# I2CHubLogicLevel.net
KiCad netlist of a schematic drawn in EAGLE
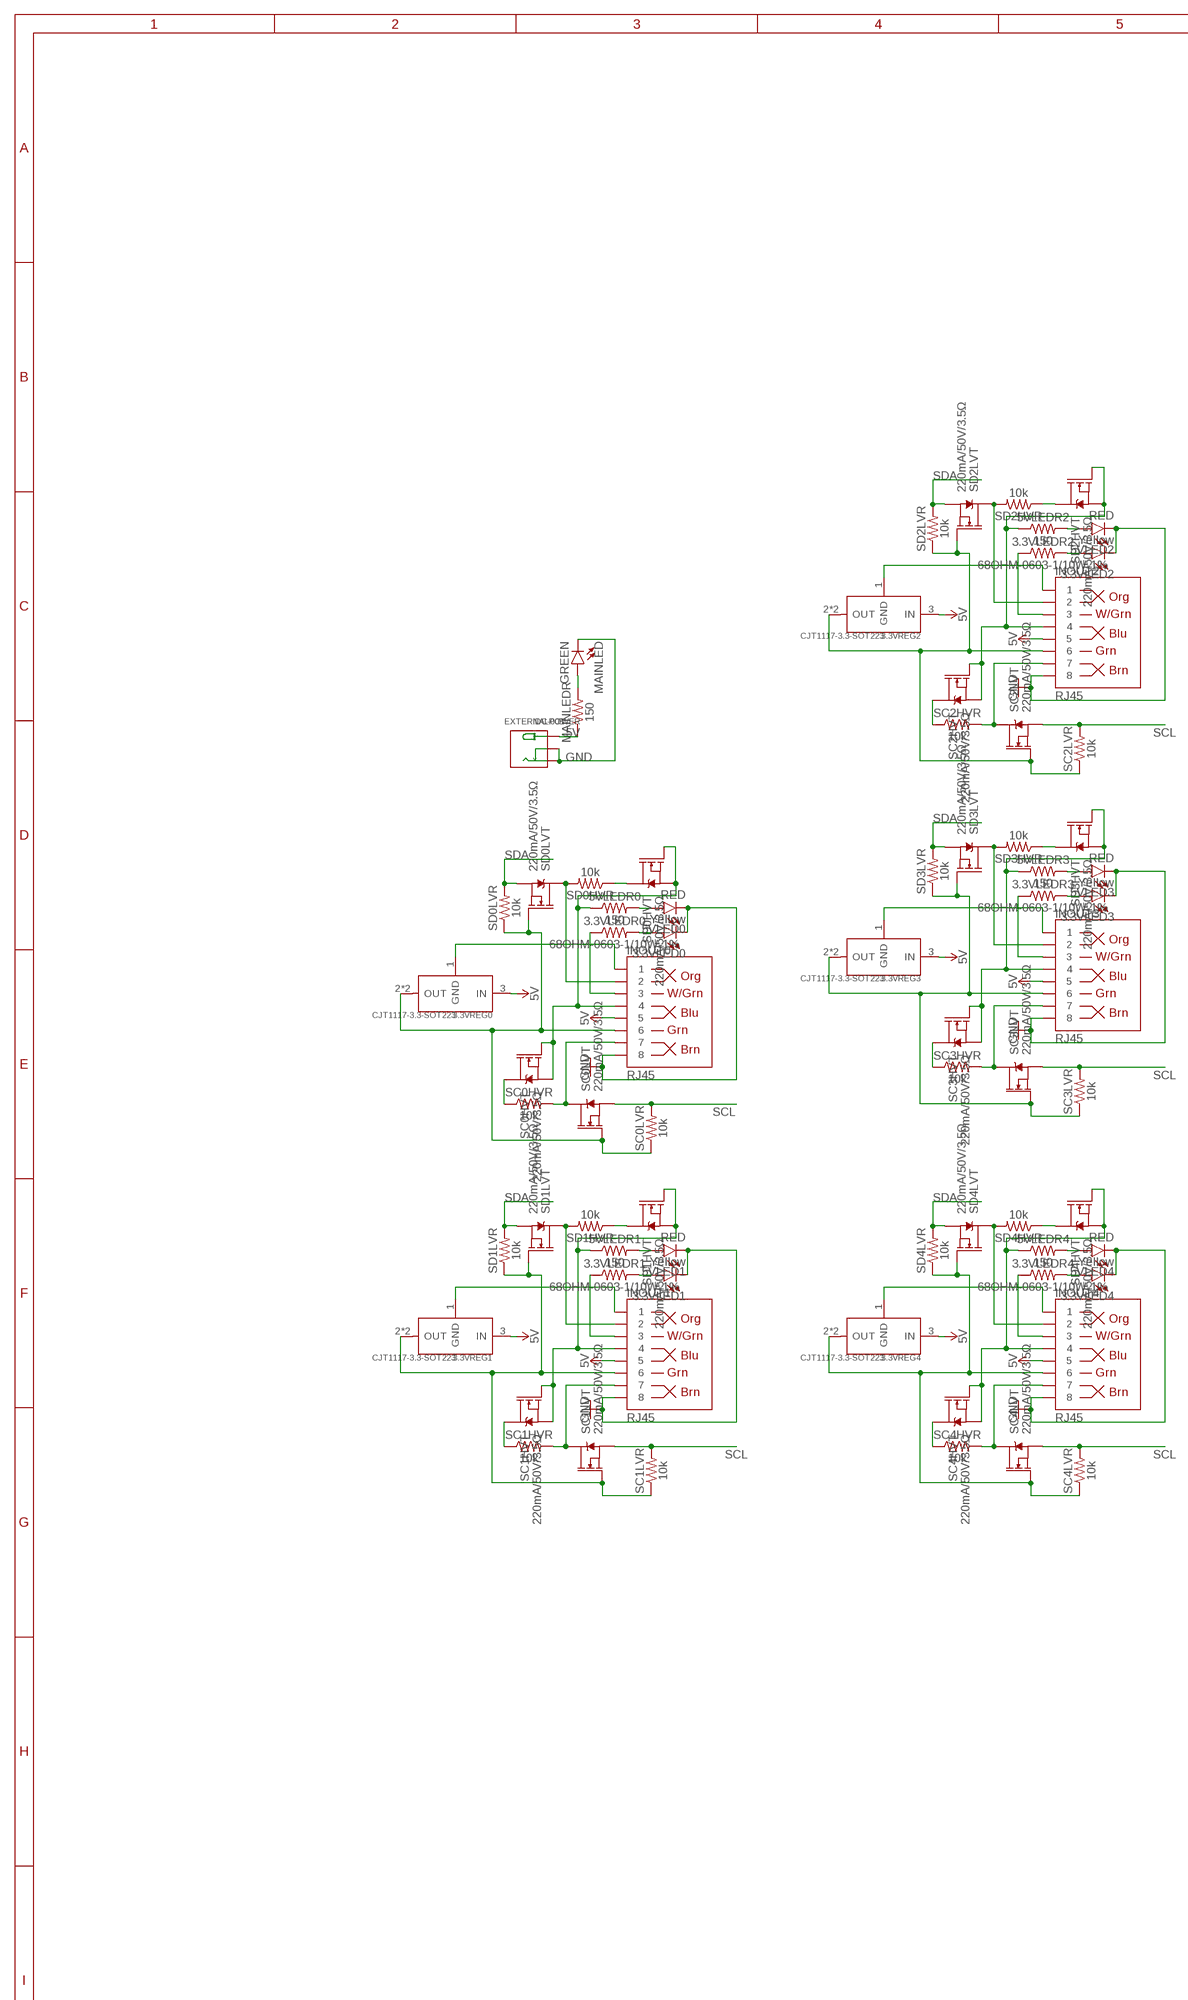
[diagram p0: schematic, sheet 1, part 1 of 2]
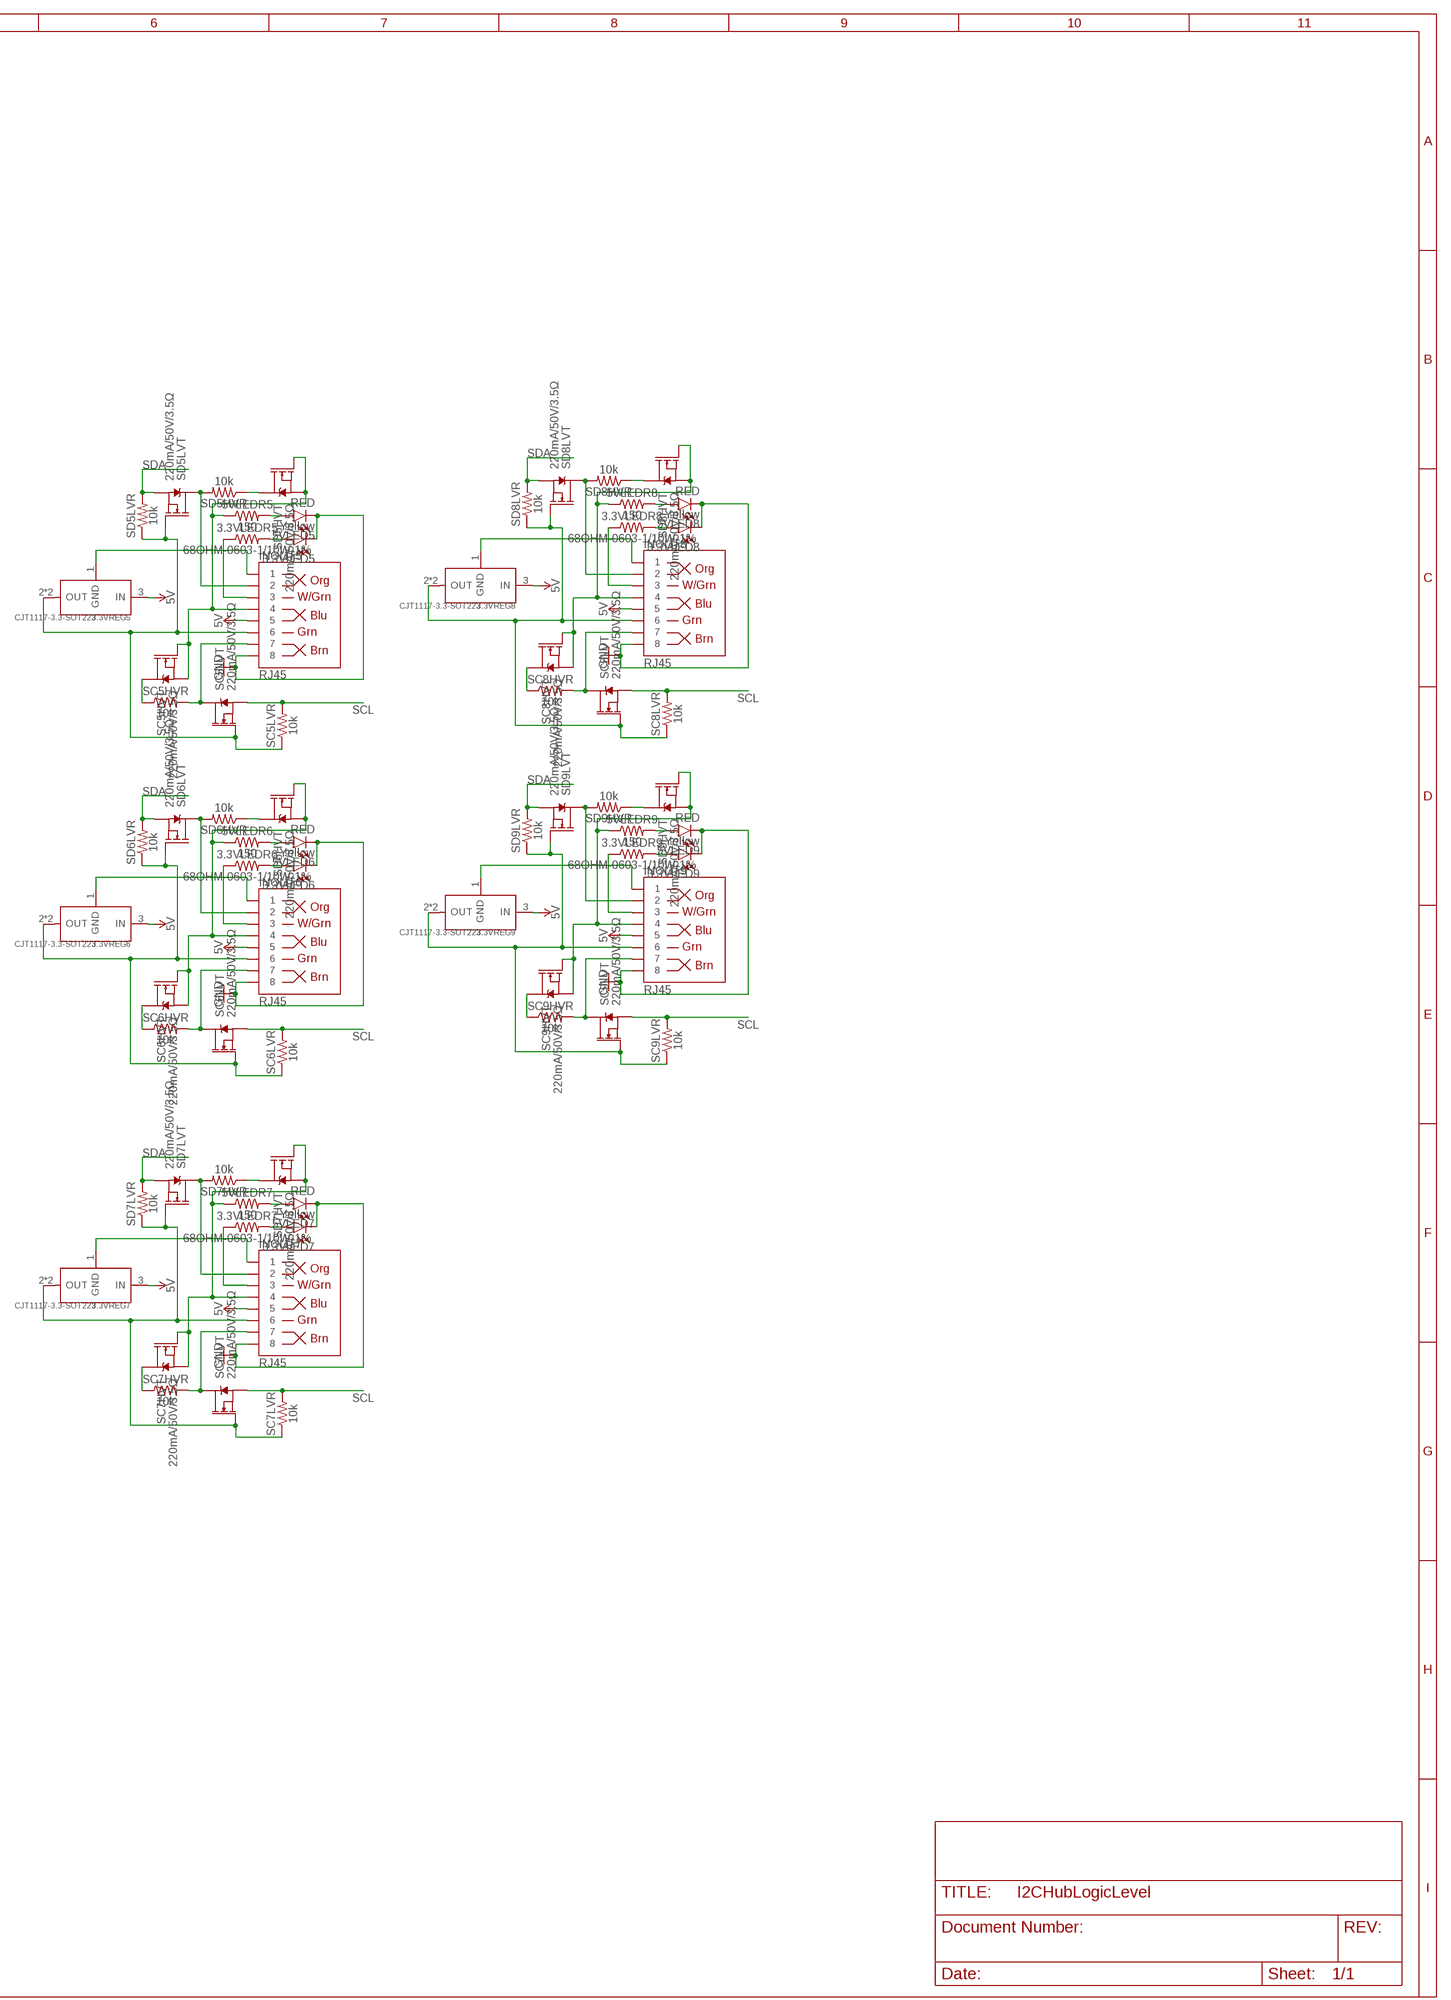
[diagram p1: schematic, sheet 1, part 2 of 2]

(export (version "E")
  (design (tool "Eeschema 10.0.6"))
  (components
    (comp (ref "3.3VLED0")
      (value "Yellow")
      (footprint "eagle-import:LED-0603")
      (libsource (lib "eagle-import") (part "LED-YELLOW0603"))
    )
    (comp (ref "3.3VLED1")
      (value "Yellow")
      (footprint "eagle-import:LED-0603")
      (libsource (lib "eagle-import") (part "LED-YELLOW0603"))
    )
    (comp (ref "3.3VLED2")
      (value "Yellow")
      (footprint "eagle-import:LED-0603")
      (libsource (lib "eagle-import") (part "LED-YELLOW0603"))
    )
    (comp (ref "3.3VLED3")
      (value "Yellow")
      (footprint "eagle-import:LED-0603")
      (libsource (lib "eagle-import") (part "LED-YELLOW0603"))
    )
    (comp (ref "3.3VLED4")
      (value "Yellow")
      (footprint "eagle-import:LED-0603")
      (libsource (lib "eagle-import") (part "LED-YELLOW0603"))
    )
    (comp (ref "3.3VLED5")
      (value "Yellow")
      (footprint "eagle-import:LED-0603")
      (libsource (lib "eagle-import") (part "LED-YELLOW0603"))
    )
    (comp (ref "3.3VLED6")
      (value "Yellow")
      (footprint "eagle-import:LED-0603")
      (libsource (lib "eagle-import") (part "LED-YELLOW0603"))
    )
    (comp (ref "3.3VLED7")
      (value "Yellow")
      (footprint "eagle-import:LED-0603")
      (libsource (lib "eagle-import") (part "LED-YELLOW0603"))
    )
    (comp (ref "3.3VLED8")
      (value "Yellow")
      (footprint "eagle-import:LED-0603")
      (libsource (lib "eagle-import") (part "LED-YELLOW0603"))
    )
    (comp (ref "3.3VLED9")
      (value "Yellow")
      (footprint "eagle-import:LED-0603")
      (libsource (lib "eagle-import") (part "LED-YELLOW0603"))
    )
    (comp (ref "3.3VLEDR0")
      (value "68OHM-0603-1/10W-1%")
      (footprint "eagle-import:0603")
      (libsource (lib "eagle-import") (part "68OHM-0603-1/10W-1%"))
    )
    (comp (ref "3.3VLEDR1")
      (value "68OHM-0603-1/10W-1%")
      (footprint "eagle-import:0603")
      (libsource (lib "eagle-import") (part "68OHM-0603-1/10W-1%"))
    )
    (comp (ref "3.3VLEDR2")
      (value "68OHM-0603-1/10W-1%")
      (footprint "eagle-import:0603")
      (libsource (lib "eagle-import") (part "68OHM-0603-1/10W-1%"))
    )
    (comp (ref "3.3VLEDR3")
      (value "68OHM-0603-1/10W-1%")
      (footprint "eagle-import:0603")
      (libsource (lib "eagle-import") (part "68OHM-0603-1/10W-1%"))
    )
    (comp (ref "3.3VLEDR4")
      (value "68OHM-0603-1/10W-1%")
      (footprint "eagle-import:0603")
      (libsource (lib "eagle-import") (part "68OHM-0603-1/10W-1%"))
    )
    (comp (ref "3.3VLEDR5")
      (value "68OHM-0603-1/10W-1%")
      (footprint "eagle-import:0603")
      (libsource (lib "eagle-import") (part "68OHM-0603-1/10W-1%"))
    )
    (comp (ref "3.3VLEDR6")
      (value "68OHM-0603-1/10W-1%")
      (footprint "eagle-import:0603")
      (libsource (lib "eagle-import") (part "68OHM-0603-1/10W-1%"))
    )
    (comp (ref "3.3VLEDR7")
      (value "68OHM-0603-1/10W-1%")
      (footprint "eagle-import:0603")
      (libsource (lib "eagle-import") (part "68OHM-0603-1/10W-1%"))
    )
    (comp (ref "3.3VLEDR8")
      (value "68OHM-0603-1/10W-1%")
      (footprint "eagle-import:0603")
      (libsource (lib "eagle-import") (part "68OHM-0603-1/10W-1%"))
    )
    (comp (ref "3.3VLEDR9")
      (value "68OHM-0603-1/10W-1%")
      (footprint "eagle-import:0603")
      (libsource (lib "eagle-import") (part "68OHM-0603-1/10W-1%"))
    )
    (comp (ref "3.3VREG0")
      (value "CJT1117-3.3-SOT223")
      (footprint "eagle-import:SOT-223")
      (fields (field (name "MPN") "CJT1117-3.3"))
      (libsource (lib "eagle-import") (part "PMIC-CJT1117-3.3(SOT223)"))
    )
    (comp (ref "3.3VREG1")
      (value "CJT1117-3.3-SOT223")
      (footprint "eagle-import:SOT-223")
      (fields (field (name "MPN") "CJT1117-3.3"))
      (libsource (lib "eagle-import") (part "PMIC-CJT1117-3.3(SOT223)"))
    )
    (comp (ref "3.3VREG2")
      (value "CJT1117-3.3-SOT223")
      (footprint "eagle-import:SOT-223")
      (fields (field (name "MPN") "CJT1117-3.3"))
      (libsource (lib "eagle-import") (part "PMIC-CJT1117-3.3(SOT223)"))
    )
    (comp (ref "3.3VREG3")
      (value "CJT1117-3.3-SOT223")
      (footprint "eagle-import:SOT-223")
      (fields (field (name "MPN") "CJT1117-3.3"))
      (libsource (lib "eagle-import") (part "PMIC-CJT1117-3.3(SOT223)"))
    )
    (comp (ref "3.3VREG4")
      (value "CJT1117-3.3-SOT223")
      (footprint "eagle-import:SOT-223")
      (fields (field (name "MPN") "CJT1117-3.3"))
      (libsource (lib "eagle-import") (part "PMIC-CJT1117-3.3(SOT223)"))
    )
    (comp (ref "3.3VREG5")
      (value "CJT1117-3.3-SOT223")
      (footprint "eagle-import:SOT-223")
      (fields (field (name "MPN") "CJT1117-3.3"))
      (libsource (lib "eagle-import") (part "PMIC-CJT1117-3.3(SOT223)"))
    )
    (comp (ref "3.3VREG6")
      (value "CJT1117-3.3-SOT223")
      (footprint "eagle-import:SOT-223")
      (fields (field (name "MPN") "CJT1117-3.3"))
      (libsource (lib "eagle-import") (part "PMIC-CJT1117-3.3(SOT223)"))
    )
    (comp (ref "3.3VREG7")
      (value "CJT1117-3.3-SOT223")
      (footprint "eagle-import:SOT-223")
      (fields (field (name "MPN") "CJT1117-3.3"))
      (libsource (lib "eagle-import") (part "PMIC-CJT1117-3.3(SOT223)"))
    )
    (comp (ref "3.3VREG8")
      (value "CJT1117-3.3-SOT223")
      (footprint "eagle-import:SOT-223")
      (fields (field (name "MPN") "CJT1117-3.3"))
      (libsource (lib "eagle-import") (part "PMIC-CJT1117-3.3(SOT223)"))
    )
    (comp (ref "3.3VREG9")
      (value "CJT1117-3.3-SOT223")
      (footprint "eagle-import:SOT-223")
      (fields (field (name "MPN") "CJT1117-3.3"))
      (libsource (lib "eagle-import") (part "PMIC-CJT1117-3.3(SOT223)"))
    )
    (comp (ref "5VLED0")
      (value "RED")
      (footprint "eagle-import:LED-0603")
      (libsource (lib "eagle-import") (part "LED-RED0603"))
    )
    (comp (ref "5VLED1")
      (value "RED")
      (footprint "eagle-import:LED-0603")
      (libsource (lib "eagle-import") (part "LED-RED0603"))
    )
    (comp (ref "5VLED2")
      (value "RED")
      (footprint "eagle-import:LED-0603")
      (libsource (lib "eagle-import") (part "LED-RED0603"))
    )
    (comp (ref "5VLED3")
      (value "RED")
      (footprint "eagle-import:LED-0603")
      (libsource (lib "eagle-import") (part "LED-RED0603"))
    )
    (comp (ref "5VLED4")
      (value "RED")
      (footprint "eagle-import:LED-0603")
      (libsource (lib "eagle-import") (part "LED-RED0603"))
    )
    (comp (ref "5VLED5")
      (value "RED")
      (footprint "eagle-import:LED-0603")
      (libsource (lib "eagle-import") (part "LED-RED0603"))
    )
    (comp (ref "5VLED6")
      (value "RED")
      (footprint "eagle-import:LED-0603")
      (libsource (lib "eagle-import") (part "LED-RED0603"))
    )
    (comp (ref "5VLED7")
      (value "RED")
      (footprint "eagle-import:LED-0603")
      (libsource (lib "eagle-import") (part "LED-RED0603"))
    )
    (comp (ref "5VLED8")
      (value "RED")
      (footprint "eagle-import:LED-0603")
      (libsource (lib "eagle-import") (part "LED-RED0603"))
    )
    (comp (ref "5VLED9")
      (value "RED")
      (footprint "eagle-import:LED-0603")
      (libsource (lib "eagle-import") (part "LED-RED0603"))
    )
    (comp (ref "5VLEDR0")
      (value "150")
      (footprint "eagle-import:0603")
      (libsource (lib "eagle-import") (part "150OHM-0603-1/10W-1%"))
    )
    (comp (ref "5VLEDR1")
      (value "150")
      (footprint "eagle-import:0603")
      (libsource (lib "eagle-import") (part "150OHM-0603-1/10W-1%"))
    )
    (comp (ref "5VLEDR2")
      (value "150")
      (footprint "eagle-import:0603")
      (libsource (lib "eagle-import") (part "150OHM-0603-1/10W-1%"))
    )
    (comp (ref "5VLEDR3")
      (value "150")
      (footprint "eagle-import:0603")
      (libsource (lib "eagle-import") (part "150OHM-0603-1/10W-1%"))
    )
    (comp (ref "5VLEDR4")
      (value "150")
      (footprint "eagle-import:0603")
      (libsource (lib "eagle-import") (part "150OHM-0603-1/10W-1%"))
    )
    (comp (ref "5VLEDR5")
      (value "150")
      (footprint "eagle-import:0603")
      (libsource (lib "eagle-import") (part "150OHM-0603-1/10W-1%"))
    )
    (comp (ref "5VLEDR6")
      (value "150")
      (footprint "eagle-import:0603")
      (libsource (lib "eagle-import") (part "150OHM-0603-1/10W-1%"))
    )
    (comp (ref "5VLEDR7")
      (value "150")
      (footprint "eagle-import:0603")
      (libsource (lib "eagle-import") (part "150OHM-0603-1/10W-1%"))
    )
    (comp (ref "5VLEDR8")
      (value "150")
      (footprint "eagle-import:0603")
      (libsource (lib "eagle-import") (part "150OHM-0603-1/10W-1%"))
    )
    (comp (ref "5VLEDR9")
      (value "150")
      (footprint "eagle-import:0603")
      (libsource (lib "eagle-import") (part "150OHM-0603-1/10W-1%"))
    )
    (comp (ref "EXTERNALPOWER")
      (value "DC-005")
      (footprint "eagle-import:DCJ3P-14.2X11.0X9.0MM")
      (libsource (lib "eagle-import") (part "CONN-POWER-JACK-2.1MM(DC-005)"))
    )
    (comp (ref "INOUT0")
      (value "RJ45")
      (footprint "eagle-import:RJ45-8")
      (libsource (lib "eagle-import") (part "RJ45-8"))
    )
    (comp (ref "INOUT1")
      (value "RJ45")
      (footprint "eagle-import:RJ45-8")
      (libsource (lib "eagle-import") (part "RJ45-8"))
    )
    (comp (ref "INOUT2")
      (value "RJ45")
      (footprint "eagle-import:RJ45-8")
      (libsource (lib "eagle-import") (part "RJ45-8"))
    )
    (comp (ref "INOUT3")
      (value "RJ45")
      (footprint "eagle-import:RJ45-8")
      (libsource (lib "eagle-import") (part "RJ45-8"))
    )
    (comp (ref "INOUT4")
      (value "RJ45")
      (footprint "eagle-import:RJ45-8")
      (libsource (lib "eagle-import") (part "RJ45-8"))
    )
    (comp (ref "INOUT5")
      (value "RJ45")
      (footprint "eagle-import:RJ45-8")
      (libsource (lib "eagle-import") (part "RJ45-8"))
    )
    (comp (ref "INOUT6")
      (value "RJ45")
      (footprint "eagle-import:RJ45-8")
      (libsource (lib "eagle-import") (part "RJ45-8"))
    )
    (comp (ref "INOUT7")
      (value "RJ45")
      (footprint "eagle-import:RJ45-8")
      (libsource (lib "eagle-import") (part "RJ45-8"))
    )
    (comp (ref "INOUT8")
      (value "RJ45")
      (footprint "eagle-import:RJ45-8")
      (libsource (lib "eagle-import") (part "RJ45-8"))
    )
    (comp (ref "INOUT9")
      (value "RJ45")
      (footprint "eagle-import:RJ45-8")
      (libsource (lib "eagle-import") (part "RJ45-8"))
    )
    (comp (ref "MAINLED")
      (value "GREEN")
      (footprint "eagle-import:LED-0603")
      (libsource (lib "eagle-import") (part "LED-GREEN0603"))
    )
    (comp (ref "MAINLEDR")
      (value "150")
      (footprint "eagle-import:0603")
      (libsource (lib "eagle-import") (part "150OHM-0603-1/10W-1%"))
    )
    (comp (ref "SC0HVR")
      (value "10k")
      (footprint "eagle-import:0603")
      (libsource (lib "eagle-import") (part "10KOHM-0603-1/10W-1%"))
    )
    (comp (ref "SC0HVT")
      (value "220mA/50V/3.5Ω")
      (footprint "eagle-import:SOT23-3")
      (libsource (lib "eagle-import") (part "MOSFET-NCH-BSS138"))
    )
    (comp (ref "SC0LVR")
      (value "10k")
      (footprint "eagle-import:0603")
      (libsource (lib "eagle-import") (part "10KOHM-0603-1/10W-1%"))
    )
    (comp (ref "SC0LVT")
      (value "220mA/50V/3.5Ω")
      (footprint "eagle-import:SOT23-3")
      (libsource (lib "eagle-import") (part "MOSFET-NCH-BSS138"))
    )
    (comp (ref "SC1HVR")
      (value "10k")
      (footprint "eagle-import:0603")
      (libsource (lib "eagle-import") (part "10KOHM-0603-1/10W-1%"))
    )
    (comp (ref "SC1HVT")
      (value "220mA/50V/3.5Ω")
      (footprint "eagle-import:SOT23-3")
      (libsource (lib "eagle-import") (part "MOSFET-NCH-BSS138"))
    )
    (comp (ref "SC1LVR")
      (value "10k")
      (footprint "eagle-import:0603")
      (libsource (lib "eagle-import") (part "10KOHM-0603-1/10W-1%"))
    )
    (comp (ref "SC1LVT")
      (value "220mA/50V/3.5Ω")
      (footprint "eagle-import:SOT23-3")
      (libsource (lib "eagle-import") (part "MOSFET-NCH-BSS138"))
    )
    (comp (ref "SC2HVR")
      (value "10k")
      (footprint "eagle-import:0603")
      (libsource (lib "eagle-import") (part "10KOHM-0603-1/10W-1%"))
    )
    (comp (ref "SC2HVT")
      (value "220mA/50V/3.5Ω")
      (footprint "eagle-import:SOT23-3")
      (libsource (lib "eagle-import") (part "MOSFET-NCH-BSS138"))
    )
    (comp (ref "SC2LVR")
      (value "10k")
      (footprint "eagle-import:0603")
      (libsource (lib "eagle-import") (part "10KOHM-0603-1/10W-1%"))
    )
    (comp (ref "SC2LVT")
      (value "220mA/50V/3.5Ω")
      (footprint "eagle-import:SOT23-3")
      (libsource (lib "eagle-import") (part "MOSFET-NCH-BSS138"))
    )
    (comp (ref "SC3HVR")
      (value "10k")
      (footprint "eagle-import:0603")
      (libsource (lib "eagle-import") (part "10KOHM-0603-1/10W-1%"))
    )
    (comp (ref "SC3HVT")
      (value "220mA/50V/3.5Ω")
      (footprint "eagle-import:SOT23-3")
      (libsource (lib "eagle-import") (part "MOSFET-NCH-BSS138"))
    )
    (comp (ref "SC3LVR")
      (value "10k")
      (footprint "eagle-import:0603")
      (libsource (lib "eagle-import") (part "10KOHM-0603-1/10W-1%"))
    )
    (comp (ref "SC3LVT")
      (value "220mA/50V/3.5Ω")
      (footprint "eagle-import:SOT23-3")
      (libsource (lib "eagle-import") (part "MOSFET-NCH-BSS138"))
    )
    (comp (ref "SC4HVR")
      (value "10k")
      (footprint "eagle-import:0603")
      (libsource (lib "eagle-import") (part "10KOHM-0603-1/10W-1%"))
    )
    (comp (ref "SC4HVT")
      (value "220mA/50V/3.5Ω")
      (footprint "eagle-import:SOT23-3")
      (libsource (lib "eagle-import") (part "MOSFET-NCH-BSS138"))
    )
    (comp (ref "SC4LVR")
      (value "10k")
      (footprint "eagle-import:0603")
      (libsource (lib "eagle-import") (part "10KOHM-0603-1/10W-1%"))
    )
    (comp (ref "SC4LVT")
      (value "220mA/50V/3.5Ω")
      (footprint "eagle-import:SOT23-3")
      (libsource (lib "eagle-import") (part "MOSFET-NCH-BSS138"))
    )
    (comp (ref "SC5HVR")
      (value "10k")
      (footprint "eagle-import:0603")
      (libsource (lib "eagle-import") (part "10KOHM-0603-1/10W-1%"))
    )
    (comp (ref "SC5HVT")
      (value "220mA/50V/3.5Ω")
      (footprint "eagle-import:SOT23-3")
      (libsource (lib "eagle-import") (part "MOSFET-NCH-BSS138"))
    )
    (comp (ref "SC5LVR")
      (value "10k")
      (footprint "eagle-import:0603")
      (libsource (lib "eagle-import") (part "10KOHM-0603-1/10W-1%"))
    )
    (comp (ref "SC5LVT")
      (value "220mA/50V/3.5Ω")
      (footprint "eagle-import:SOT23-3")
      (libsource (lib "eagle-import") (part "MOSFET-NCH-BSS138"))
    )
    (comp (ref "SC6HVR")
      (value "10k")
      (footprint "eagle-import:0603")
      (libsource (lib "eagle-import") (part "10KOHM-0603-1/10W-1%"))
    )
    (comp (ref "SC6HVT")
      (value "220mA/50V/3.5Ω")
      (footprint "eagle-import:SOT23-3")
      (libsource (lib "eagle-import") (part "MOSFET-NCH-BSS138"))
    )
    (comp (ref "SC6LVR")
      (value "10k")
      (footprint "eagle-import:0603")
      (libsource (lib "eagle-import") (part "10KOHM-0603-1/10W-1%"))
    )
    (comp (ref "SC6LVT")
      (value "220mA/50V/3.5Ω")
      (footprint "eagle-import:SOT23-3")
      (libsource (lib "eagle-import") (part "MOSFET-NCH-BSS138"))
    )
    (comp (ref "SC7HVR")
      (value "10k")
      (footprint "eagle-import:0603")
      (libsource (lib "eagle-import") (part "10KOHM-0603-1/10W-1%"))
    )
    (comp (ref "SC7HVT")
      (value "220mA/50V/3.5Ω")
      (footprint "eagle-import:SOT23-3")
      (libsource (lib "eagle-import") (part "MOSFET-NCH-BSS138"))
    )
    (comp (ref "SC7LVR")
      (value "10k")
      (footprint "eagle-import:0603")
      (libsource (lib "eagle-import") (part "10KOHM-0603-1/10W-1%"))
    )
    (comp (ref "SC7LVT")
      (value "220mA/50V/3.5Ω")
      (footprint "eagle-import:SOT23-3")
      (libsource (lib "eagle-import") (part "MOSFET-NCH-BSS138"))
    )
    (comp (ref "SC8HVR")
      (value "10k")
      (footprint "eagle-import:0603")
      (libsource (lib "eagle-import") (part "10KOHM-0603-1/10W-1%"))
    )
    (comp (ref "SC8HVT")
      (value "220mA/50V/3.5Ω")
      (footprint "eagle-import:SOT23-3")
      (libsource (lib "eagle-import") (part "MOSFET-NCH-BSS138"))
    )
    (comp (ref "SC8LVR")
      (value "10k")
      (footprint "eagle-import:0603")
      (libsource (lib "eagle-import") (part "10KOHM-0603-1/10W-1%"))
    )
    (comp (ref "SC8LVT")
      (value "220mA/50V/3.5Ω")
      (footprint "eagle-import:SOT23-3")
      (libsource (lib "eagle-import") (part "MOSFET-NCH-BSS138"))
    )
    (comp (ref "SC9HVR")
      (value "10k")
      (footprint "eagle-import:0603")
      (libsource (lib "eagle-import") (part "10KOHM-0603-1/10W-1%"))
    )
    (comp (ref "SC9HVT")
      (value "220mA/50V/3.5Ω")
      (footprint "eagle-import:SOT23-3")
      (libsource (lib "eagle-import") (part "MOSFET-NCH-BSS138"))
    )
    (comp (ref "SC9LVR")
      (value "10k")
      (footprint "eagle-import:0603")
      (libsource (lib "eagle-import") (part "10KOHM-0603-1/10W-1%"))
    )
    (comp (ref "SC9LVT")
      (value "220mA/50V/3.5Ω")
      (footprint "eagle-import:SOT23-3")
      (libsource (lib "eagle-import") (part "MOSFET-NCH-BSS138"))
    )
    (comp (ref "SD0HVR")
      (value "10k")
      (footprint "eagle-import:0603")
      (libsource (lib "eagle-import") (part "10KOHM-0603-1/10W-1%"))
    )
    (comp (ref "SD0HVT")
      (value "220mA/50V/3.5Ω")
      (footprint "eagle-import:SOT23-3")
      (libsource (lib "eagle-import") (part "MOSFET-NCH-BSS138"))
    )
    (comp (ref "SD0LVR")
      (value "10k")
      (footprint "eagle-import:0603")
      (libsource (lib "eagle-import") (part "10KOHM-0603-1/10W-1%"))
    )
    (comp (ref "SD0LVT")
      (value "220mA/50V/3.5Ω")
      (footprint "eagle-import:SOT23-3")
      (libsource (lib "eagle-import") (part "MOSFET-NCH-BSS138"))
    )
    (comp (ref "SD1HVR")
      (value "10k")
      (footprint "eagle-import:0603")
      (libsource (lib "eagle-import") (part "10KOHM-0603-1/10W-1%"))
    )
    (comp (ref "SD1HVT")
      (value "220mA/50V/3.5Ω")
      (footprint "eagle-import:SOT23-3")
      (libsource (lib "eagle-import") (part "MOSFET-NCH-BSS138"))
    )
    (comp (ref "SD1LVR")
      (value "10k")
      (footprint "eagle-import:0603")
      (libsource (lib "eagle-import") (part "10KOHM-0603-1/10W-1%"))
    )
    (comp (ref "SD1LVT")
      (value "220mA/50V/3.5Ω")
      (footprint "eagle-import:SOT23-3")
      (libsource (lib "eagle-import") (part "MOSFET-NCH-BSS138"))
    )
    (comp (ref "SD2HVR")
      (value "10k")
      (footprint "eagle-import:0603")
      (libsource (lib "eagle-import") (part "10KOHM-0603-1/10W-1%"))
    )
    (comp (ref "SD2HVT")
      (value "220mA/50V/3.5Ω")
      (footprint "eagle-import:SOT23-3")
      (libsource (lib "eagle-import") (part "MOSFET-NCH-BSS138"))
    )
    (comp (ref "SD2LVR")
      (value "10k")
      (footprint "eagle-import:0603")
      (libsource (lib "eagle-import") (part "10KOHM-0603-1/10W-1%"))
    )
    (comp (ref "SD2LVT")
      (value "220mA/50V/3.5Ω")
      (footprint "eagle-import:SOT23-3")
      (libsource (lib "eagle-import") (part "MOSFET-NCH-BSS138"))
    )
    (comp (ref "SD3HVR")
      (value "10k")
      (footprint "eagle-import:0603")
      (libsource (lib "eagle-import") (part "10KOHM-0603-1/10W-1%"))
    )
    (comp (ref "SD3HVT")
      (value "220mA/50V/3.5Ω")
      (footprint "eagle-import:SOT23-3")
      (libsource (lib "eagle-import") (part "MOSFET-NCH-BSS138"))
    )
    (comp (ref "SD3LVR")
      (value "10k")
      (footprint "eagle-import:0603")
      (libsource (lib "eagle-import") (part "10KOHM-0603-1/10W-1%"))
    )
    (comp (ref "SD3LVT")
      (value "220mA/50V/3.5Ω")
      (footprint "eagle-import:SOT23-3")
      (libsource (lib "eagle-import") (part "MOSFET-NCH-BSS138"))
    )
    (comp (ref "SD4HVR")
      (value "10k")
      (footprint "eagle-import:0603")
      (libsource (lib "eagle-import") (part "10KOHM-0603-1/10W-1%"))
    )
    (comp (ref "SD4HVT")
      (value "220mA/50V/3.5Ω")
      (footprint "eagle-import:SOT23-3")
      (libsource (lib "eagle-import") (part "MOSFET-NCH-BSS138"))
    )
    (comp (ref "SD4LVR")
      (value "10k")
      (footprint "eagle-import:0603")
      (libsource (lib "eagle-import") (part "10KOHM-0603-1/10W-1%"))
    )
    (comp (ref "SD4LVT")
      (value "220mA/50V/3.5Ω")
      (footprint "eagle-import:SOT23-3")
      (libsource (lib "eagle-import") (part "MOSFET-NCH-BSS138"))
    )
    (comp (ref "SD5HVR")
      (value "10k")
      (footprint "eagle-import:0603")
      (libsource (lib "eagle-import") (part "10KOHM-0603-1/10W-1%"))
    )
    (comp (ref "SD5HVT")
      (value "220mA/50V/3.5Ω")
      (footprint "eagle-import:SOT23-3")
      (libsource (lib "eagle-import") (part "MOSFET-NCH-BSS138"))
    )
    (comp (ref "SD5LVR")
      (value "10k")
      (footprint "eagle-import:0603")
      (libsource (lib "eagle-import") (part "10KOHM-0603-1/10W-1%"))
    )
    (comp (ref "SD5LVT")
      (value "220mA/50V/3.5Ω")
      (footprint "eagle-import:SOT23-3")
      (libsource (lib "eagle-import") (part "MOSFET-NCH-BSS138"))
    )
    (comp (ref "SD6HVR")
      (value "10k")
      (footprint "eagle-import:0603")
      (libsource (lib "eagle-import") (part "10KOHM-0603-1/10W-1%"))
    )
    (comp (ref "SD6HVT")
      (value "220mA/50V/3.5Ω")
      (footprint "eagle-import:SOT23-3")
      (libsource (lib "eagle-import") (part "MOSFET-NCH-BSS138"))
    )
    (comp (ref "SD6LVR")
      (value "10k")
      (footprint "eagle-import:0603")
      (libsource (lib "eagle-import") (part "10KOHM-0603-1/10W-1%"))
    )
    (comp (ref "SD6LVT")
      (value "220mA/50V/3.5Ω")
      (footprint "eagle-import:SOT23-3")
      (libsource (lib "eagle-import") (part "MOSFET-NCH-BSS138"))
    )
    (comp (ref "SD7HVR")
      (value "10k")
      (footprint "eagle-import:0603")
      (libsource (lib "eagle-import") (part "10KOHM-0603-1/10W-1%"))
    )
    (comp (ref "SD7HVT")
      (value "220mA/50V/3.5Ω")
      (footprint "eagle-import:SOT23-3")
      (libsource (lib "eagle-import") (part "MOSFET-NCH-BSS138"))
    )
    (comp (ref "SD7LVR")
      (value "10k")
      (footprint "eagle-import:0603")
      (libsource (lib "eagle-import") (part "10KOHM-0603-1/10W-1%"))
    )
    (comp (ref "SD7LVT")
      (value "220mA/50V/3.5Ω")
      (footprint "eagle-import:SOT23-3")
      (libsource (lib "eagle-import") (part "MOSFET-NCH-BSS138"))
    )
    (comp (ref "SD8HVR")
      (value "10k")
      (footprint "eagle-import:0603")
      (libsource (lib "eagle-import") (part "10KOHM-0603-1/10W-1%"))
    )
    (comp (ref "SD8HVT")
      (value "220mA/50V/3.5Ω")
      (footprint "eagle-import:SOT23-3")
      (libsource (lib "eagle-import") (part "MOSFET-NCH-BSS138"))
    )
    (comp (ref "SD8LVR")
      (value "10k")
      (footprint "eagle-import:0603")
      (libsource (lib "eagle-import") (part "10KOHM-0603-1/10W-1%"))
    )
    (comp (ref "SD8LVT")
      (value "220mA/50V/3.5Ω")
      (footprint "eagle-import:SOT23-3")
      (libsource (lib "eagle-import") (part "MOSFET-NCH-BSS138"))
    )
    (comp (ref "SD9HVR")
      (value "10k")
      (footprint "eagle-import:0603")
      (libsource (lib "eagle-import") (part "10KOHM-0603-1/10W-1%"))
    )
    (comp (ref "SD9HVT")
      (value "220mA/50V/3.5Ω")
      (footprint "eagle-import:SOT23-3")
      (libsource (lib "eagle-import") (part "MOSFET-NCH-BSS138"))
    )
    (comp (ref "SD9LVR")
      (value "10k")
      (footprint "eagle-import:0603")
      (libsource (lib "eagle-import") (part "10KOHM-0603-1/10W-1%"))
    )
    (comp (ref "SD9LVT")
      (value "220mA/50V/3.5Ω")
      (footprint "eagle-import:SOT23-3")
      (libsource (lib "eagle-import") (part "MOSFET-NCH-BSS138"))
    )
  )
  (nets
    (net (code "1") (name "/SCL") (class "Default")
      (node (ref "SC0LVR") (pin "2") (pinfunction "2_2") (pintype "passive"))
      (node (ref "SC0LVT") (pin "2") (pinfunction "S_2") (pintype "bidirectional"))
      (node (ref "SC1LVR") (pin "2") (pinfunction "2_2") (pintype "passive"))
      (node (ref "SC1LVT") (pin "2") (pinfunction "S_2") (pintype "bidirectional"))
      (node (ref "SC2LVR") (pin "2") (pinfunction "2_2") (pintype "passive"))
      (node (ref "SC2LVT") (pin "2") (pinfunction "S_2") (pintype "bidirectional"))
      (node (ref "SC3LVR") (pin "2") (pinfunction "2_2") (pintype "passive"))
      (node (ref "SC3LVT") (pin "2") (pinfunction "S_2") (pintype "bidirectional"))
      (node (ref "SC4LVR") (pin "2") (pinfunction "2_2") (pintype "passive"))
      (node (ref "SC4LVT") (pin "2") (pinfunction "S_2") (pintype "bidirectional"))
      (node (ref "SC5LVR") (pin "2") (pinfunction "2_2") (pintype "passive"))
      (node (ref "SC5LVT") (pin "2") (pinfunction "S_2") (pintype "bidirectional"))
      (node (ref "SC6LVR") (pin "2") (pinfunction "2_2") (pintype "passive"))
      (node (ref "SC6LVT") (pin "2") (pinfunction "S_2") (pintype "bidirectional"))
      (node (ref "SC7LVR") (pin "2") (pinfunction "2_2") (pintype "passive"))
      (node (ref "SC7LVT") (pin "2") (pinfunction "S_2") (pintype "bidirectional"))
      (node (ref "SC8LVR") (pin "2") (pinfunction "2_2") (pintype "passive"))
      (node (ref "SC8LVT") (pin "2") (pinfunction "S_2") (pintype "bidirectional"))
      (node (ref "SC9LVR") (pin "2") (pinfunction "2_2") (pintype "passive"))
      (node (ref "SC9LVT") (pin "2") (pinfunction "S_2") (pintype "bidirectional"))
    )
    (net (code "2") (name "/SDA") (class "Default")
      (node (ref "SD0LVR") (pin "2") (pinfunction "2_2") (pintype "passive"))
      (node (ref "SD0LVT") (pin "2") (pinfunction "S_2") (pintype "bidirectional"))
      (node (ref "SD1LVR") (pin "2") (pinfunction "2_2") (pintype "passive"))
      (node (ref "SD1LVT") (pin "2") (pinfunction "S_2") (pintype "bidirectional"))
      (node (ref "SD2LVR") (pin "2") (pinfunction "2_2") (pintype "passive"))
      (node (ref "SD2LVT") (pin "2") (pinfunction "S_2") (pintype "bidirectional"))
      (node (ref "SD3LVR") (pin "2") (pinfunction "2_2") (pintype "passive"))
      (node (ref "SD3LVT") (pin "2") (pinfunction "S_2") (pintype "bidirectional"))
      (node (ref "SD4LVR") (pin "2") (pinfunction "2_2") (pintype "passive"))
      (node (ref "SD4LVT") (pin "2") (pinfunction "S_2") (pintype "bidirectional"))
      (node (ref "SD5LVR") (pin "2") (pinfunction "2_2") (pintype "passive"))
      (node (ref "SD5LVT") (pin "2") (pinfunction "S_2") (pintype "bidirectional"))
      (node (ref "SD6LVR") (pin "2") (pinfunction "2_2") (pintype "passive"))
      (node (ref "SD6LVT") (pin "2") (pinfunction "S_2") (pintype "bidirectional"))
      (node (ref "SD7LVR") (pin "2") (pinfunction "2_2") (pintype "passive"))
      (node (ref "SD7LVT") (pin "2") (pinfunction "S_2") (pintype "bidirectional"))
      (node (ref "SD8LVR") (pin "2") (pinfunction "2_2") (pintype "passive"))
      (node (ref "SD8LVT") (pin "2") (pinfunction "S_2") (pintype "bidirectional"))
      (node (ref "SD9LVR") (pin "2") (pinfunction "2_2") (pintype "passive"))
      (node (ref "SD9LVT") (pin "2") (pinfunction "S_2") (pintype "bidirectional"))
    )
    (net (code "3") (name "5V") (class "Default")
      (node (ref "3.3VREG0") (pin "3") (pinfunction "IN_3") (pintype "bidirectional"))
      (node (ref "3.3VREG1") (pin "3") (pinfunction "IN_3") (pintype "bidirectional"))
      (node (ref "3.3VREG2") (pin "3") (pinfunction "IN_3") (pintype "bidirectional"))
      (node (ref "3.3VREG3") (pin "3") (pinfunction "IN_3") (pintype "bidirectional"))
      (node (ref "3.3VREG4") (pin "3") (pinfunction "IN_3") (pintype "bidirectional"))
      (node (ref "3.3VREG5") (pin "3") (pinfunction "IN_3") (pintype "bidirectional"))
      (node (ref "3.3VREG6") (pin "3") (pinfunction "IN_3") (pintype "bidirectional"))
      (node (ref "3.3VREG7") (pin "3") (pinfunction "IN_3") (pintype "bidirectional"))
      (node (ref "3.3VREG8") (pin "3") (pinfunction "IN_3") (pintype "bidirectional"))
      (node (ref "3.3VREG9") (pin "3") (pinfunction "IN_3") (pintype "bidirectional"))
      (node (ref "EXTERNALPOWER") (pin "+") (pinfunction "+_+") (pintype "bidirectional"))
      (node (ref "INOUT0") (pin "5") (pinfunction "5_5") (pintype "bidirectional"))
      (node (ref "INOUT1") (pin "5") (pinfunction "5_5") (pintype "bidirectional"))
      (node (ref "INOUT2") (pin "5") (pinfunction "5_5") (pintype "bidirectional"))
      (node (ref "INOUT3") (pin "5") (pinfunction "5_5") (pintype "bidirectional"))
      (node (ref "INOUT4") (pin "5") (pinfunction "5_5") (pintype "bidirectional"))
      (node (ref "INOUT5") (pin "5") (pinfunction "5_5") (pintype "bidirectional"))
      (node (ref "INOUT6") (pin "5") (pinfunction "5_5") (pintype "bidirectional"))
      (node (ref "INOUT7") (pin "5") (pinfunction "5_5") (pintype "bidirectional"))
      (node (ref "INOUT8") (pin "5") (pinfunction "5_5") (pintype "bidirectional"))
      (node (ref "INOUT9") (pin "5") (pinfunction "5_5") (pintype "bidirectional"))
      (node (ref "MAINLEDR") (pin "1") (pinfunction "1_1") (pintype "passive"))
    )
    (net (code "4") (name "GND") (class "Default")
      (node (ref "3.3VLED0") (pin "C") (pinfunction "C_C") (pintype "passive"))
      (node (ref "3.3VLED1") (pin "C") (pinfunction "C_C") (pintype "passive"))
      (node (ref "3.3VLED2") (pin "C") (pinfunction "C_C") (pintype "passive"))
      (node (ref "3.3VLED3") (pin "C") (pinfunction "C_C") (pintype "passive"))
      (node (ref "3.3VLED4") (pin "C") (pinfunction "C_C") (pintype "passive"))
      (node (ref "3.3VLED5") (pin "C") (pinfunction "C_C") (pintype "passive"))
      (node (ref "3.3VLED6") (pin "C") (pinfunction "C_C") (pintype "passive"))
      (node (ref "3.3VLED7") (pin "C") (pinfunction "C_C") (pintype "passive"))
      (node (ref "3.3VLED8") (pin "C") (pinfunction "C_C") (pintype "passive"))
      (node (ref "3.3VLED9") (pin "C") (pinfunction "C_C") (pintype "passive"))
      (node (ref "5VLED0") (pin "C") (pinfunction "C_C") (pintype "passive"))
      (node (ref "5VLED1") (pin "C") (pinfunction "C_C") (pintype "passive"))
      (node (ref "5VLED2") (pin "C") (pinfunction "C_C") (pintype "passive"))
      (node (ref "5VLED3") (pin "C") (pinfunction "C_C") (pintype "passive"))
      (node (ref "5VLED4") (pin "C") (pinfunction "C_C") (pintype "passive"))
      (node (ref "5VLED5") (pin "C") (pinfunction "C_C") (pintype "passive"))
      (node (ref "5VLED6") (pin "C") (pinfunction "C_C") (pintype "passive"))
      (node (ref "5VLED7") (pin "C") (pinfunction "C_C") (pintype "passive"))
      (node (ref "5VLED8") (pin "C") (pinfunction "C_C") (pintype "passive"))
      (node (ref "5VLED9") (pin "C") (pinfunction "C_C") (pintype "passive"))
      (node (ref "EXTERNALPOWER") (pin "-1") (pinfunction "-_-1") (pintype "bidirectional"))
      (node (ref "EXTERNALPOWER") (pin "-2") (pinfunction "CDN_-2") (pintype "bidirectional"))
      (node (ref "INOUT0") (pin "8") (pinfunction "8_8") (pintype "bidirectional"))
      (node (ref "INOUT1") (pin "8") (pinfunction "8_8") (pintype "bidirectional"))
      (node (ref "INOUT2") (pin "8") (pinfunction "8_8") (pintype "bidirectional"))
      (node (ref "INOUT3") (pin "8") (pinfunction "8_8") (pintype "bidirectional"))
      (node (ref "INOUT4") (pin "8") (pinfunction "8_8") (pintype "bidirectional"))
      (node (ref "INOUT5") (pin "8") (pinfunction "8_8") (pintype "bidirectional"))
      (node (ref "INOUT6") (pin "8") (pinfunction "8_8") (pintype "bidirectional"))
      (node (ref "INOUT7") (pin "8") (pinfunction "8_8") (pintype "bidirectional"))
      (node (ref "INOUT8") (pin "8") (pinfunction "8_8") (pintype "bidirectional"))
      (node (ref "INOUT9") (pin "8") (pinfunction "8_8") (pintype "bidirectional"))
      (node (ref "MAINLED") (pin "C") (pinfunction "C_C") (pintype "passive"))
    )
    (net (code "5") (name "Net-(3.3VLED0-PadA)") (class "Default")
      (node (ref "3.3VLED0") (pin "A") (pinfunction "A_A") (pintype "passive"))
      (node (ref "3.3VLEDR0") (pin "2") (pinfunction "2_2") (pintype "passive"))
    )
    (net (code "6") (name "Net-(3.3VLED1-PadA)") (class "Default")
      (node (ref "3.3VLED1") (pin "A") (pinfunction "A_A") (pintype "passive"))
      (node (ref "3.3VLEDR1") (pin "2") (pinfunction "2_2") (pintype "passive"))
    )
    (net (code "7") (name "Net-(3.3VLED2-PadA)") (class "Default")
      (node (ref "3.3VLED2") (pin "A") (pinfunction "A_A") (pintype "passive"))
      (node (ref "3.3VLEDR2") (pin "2") (pinfunction "2_2") (pintype "passive"))
    )
    (net (code "8") (name "Net-(3.3VLED3-PadA)") (class "Default")
      (node (ref "3.3VLED3") (pin "A") (pinfunction "A_A") (pintype "passive"))
      (node (ref "3.3VLEDR3") (pin "2") (pinfunction "2_2") (pintype "passive"))
    )
    (net (code "9") (name "Net-(3.3VLED4-PadA)") (class "Default")
      (node (ref "3.3VLED4") (pin "A") (pinfunction "A_A") (pintype "passive"))
      (node (ref "3.3VLEDR4") (pin "2") (pinfunction "2_2") (pintype "passive"))
    )
    (net (code "10") (name "Net-(3.3VLED5-PadA)") (class "Default")
      (node (ref "3.3VLED5") (pin "A") (pinfunction "A_A") (pintype "passive"))
      (node (ref "3.3VLEDR5") (pin "2") (pinfunction "2_2") (pintype "passive"))
    )
    (net (code "11") (name "Net-(3.3VLED6-PadA)") (class "Default")
      (node (ref "3.3VLED6") (pin "A") (pinfunction "A_A") (pintype "passive"))
      (node (ref "3.3VLEDR6") (pin "2") (pinfunction "2_2") (pintype "passive"))
    )
    (net (code "12") (name "Net-(3.3VLED7-PadA)") (class "Default")
      (node (ref "3.3VLED7") (pin "A") (pinfunction "A_A") (pintype "passive"))
      (node (ref "3.3VLEDR7") (pin "2") (pinfunction "2_2") (pintype "passive"))
    )
    (net (code "13") (name "Net-(3.3VLED8-PadA)") (class "Default")
      (node (ref "3.3VLED8") (pin "A") (pinfunction "A_A") (pintype "passive"))
      (node (ref "3.3VLEDR8") (pin "2") (pinfunction "2_2") (pintype "passive"))
    )
    (net (code "14") (name "Net-(3.3VLED9-PadA)") (class "Default")
      (node (ref "3.3VLED9") (pin "A") (pinfunction "A_A") (pintype "passive"))
      (node (ref "3.3VLEDR9") (pin "2") (pinfunction "2_2") (pintype "passive"))
    )
    (net (code "15") (name "Net-(3.3VLEDR0-Pad1)") (class "Default")
      (node (ref "3.3VLEDR0") (pin "1") (pinfunction "1_1") (pintype "passive"))
      (node (ref "INOUT0") (pin "3") (pinfunction "3_3") (pintype "bidirectional"))
    )
    (net (code "16") (name "Net-(3.3VLEDR1-Pad1)") (class "Default")
      (node (ref "3.3VLEDR1") (pin "1") (pinfunction "1_1") (pintype "passive"))
      (node (ref "INOUT1") (pin "3") (pinfunction "3_3") (pintype "bidirectional"))
    )
    (net (code "17") (name "Net-(3.3VLEDR2-Pad1)") (class "Default")
      (node (ref "3.3VLEDR2") (pin "1") (pinfunction "1_1") (pintype "passive"))
      (node (ref "INOUT2") (pin "3") (pinfunction "3_3") (pintype "bidirectional"))
    )
    (net (code "18") (name "Net-(3.3VLEDR3-Pad1)") (class "Default")
      (node (ref "3.3VLEDR3") (pin "1") (pinfunction "1_1") (pintype "passive"))
      (node (ref "INOUT3") (pin "3") (pinfunction "3_3") (pintype "bidirectional"))
    )
    (net (code "19") (name "Net-(3.3VLEDR4-Pad1)") (class "Default")
      (node (ref "3.3VLEDR4") (pin "1") (pinfunction "1_1") (pintype "passive"))
      (node (ref "INOUT4") (pin "3") (pinfunction "3_3") (pintype "bidirectional"))
    )
    (net (code "20") (name "Net-(3.3VLEDR5-Pad1)") (class "Default")
      (node (ref "3.3VLEDR5") (pin "1") (pinfunction "1_1") (pintype "passive"))
      (node (ref "INOUT5") (pin "3") (pinfunction "3_3") (pintype "bidirectional"))
    )
    (net (code "21") (name "Net-(3.3VLEDR6-Pad1)") (class "Default")
      (node (ref "3.3VLEDR6") (pin "1") (pinfunction "1_1") (pintype "passive"))
      (node (ref "INOUT6") (pin "3") (pinfunction "3_3") (pintype "bidirectional"))
    )
    (net (code "22") (name "Net-(3.3VLEDR7-Pad1)") (class "Default")
      (node (ref "3.3VLEDR7") (pin "1") (pinfunction "1_1") (pintype "passive"))
      (node (ref "INOUT7") (pin "3") (pinfunction "3_3") (pintype "bidirectional"))
    )
    (net (code "23") (name "Net-(3.3VLEDR8-Pad1)") (class "Default")
      (node (ref "3.3VLEDR8") (pin "1") (pinfunction "1_1") (pintype "passive"))
      (node (ref "INOUT8") (pin "3") (pinfunction "3_3") (pintype "bidirectional"))
    )
    (net (code "24") (name "Net-(3.3VLEDR9-Pad1)") (class "Default")
      (node (ref "3.3VLEDR9") (pin "1") (pinfunction "1_1") (pintype "passive"))
      (node (ref "INOUT9") (pin "3") (pinfunction "3_3") (pintype "bidirectional"))
    )
    (net (code "25") (name "Net-(3.3VREG0-GND)") (class "Default")
      (node (ref "3.3VREG0") (pin "1") (pinfunction "GND_1") (pintype "bidirectional"))
      (node (ref "INOUT0") (pin "1") (pinfunction "1_1") (pintype "bidirectional"))
    )
    (net (code "26") (name "Net-(3.3VREG1-GND)") (class "Default")
      (node (ref "3.3VREG1") (pin "1") (pinfunction "GND_1") (pintype "bidirectional"))
      (node (ref "INOUT1") (pin "1") (pinfunction "1_1") (pintype "bidirectional"))
    )
    (net (code "27") (name "Net-(3.3VREG2-GND)") (class "Default")
      (node (ref "3.3VREG2") (pin "1") (pinfunction "GND_1") (pintype "bidirectional"))
      (node (ref "INOUT2") (pin "1") (pinfunction "1_1") (pintype "bidirectional"))
    )
    (net (code "28") (name "Net-(3.3VREG3-GND)") (class "Default")
      (node (ref "3.3VREG3") (pin "1") (pinfunction "GND_1") (pintype "bidirectional"))
      (node (ref "INOUT3") (pin "1") (pinfunction "1_1") (pintype "bidirectional"))
    )
    (net (code "29") (name "Net-(3.3VREG4-GND)") (class "Default")
      (node (ref "3.3VREG4") (pin "1") (pinfunction "GND_1") (pintype "bidirectional"))
      (node (ref "INOUT4") (pin "1") (pinfunction "1_1") (pintype "bidirectional"))
    )
    (net (code "30") (name "Net-(3.3VREG5-GND)") (class "Default")
      (node (ref "3.3VREG5") (pin "1") (pinfunction "GND_1") (pintype "bidirectional"))
      (node (ref "INOUT5") (pin "1") (pinfunction "1_1") (pintype "bidirectional"))
    )
    (net (code "31") (name "Net-(3.3VREG6-GND)") (class "Default")
      (node (ref "3.3VREG6") (pin "1") (pinfunction "GND_1") (pintype "bidirectional"))
      (node (ref "INOUT6") (pin "1") (pinfunction "1_1") (pintype "bidirectional"))
    )
    (net (code "32") (name "Net-(3.3VREG7-GND)") (class "Default")
      (node (ref "3.3VREG7") (pin "1") (pinfunction "GND_1") (pintype "bidirectional"))
      (node (ref "INOUT7") (pin "1") (pinfunction "1_1") (pintype "bidirectional"))
    )
    (net (code "33") (name "Net-(3.3VREG8-GND)") (class "Default")
      (node (ref "3.3VREG8") (pin "1") (pinfunction "GND_1") (pintype "bidirectional"))
      (node (ref "INOUT8") (pin "1") (pinfunction "1_1") (pintype "bidirectional"))
    )
    (net (code "34") (name "Net-(3.3VREG9-GND)") (class "Default")
      (node (ref "3.3VREG9") (pin "1") (pinfunction "GND_1") (pintype "bidirectional"))
      (node (ref "INOUT9") (pin "1") (pinfunction "1_1") (pintype "bidirectional"))
    )
    (net (code "35") (name "Net-(5VLED0-PadA)") (class "Default")
      (node (ref "5VLED0") (pin "A") (pinfunction "A_A") (pintype "passive"))
      (node (ref "5VLEDR0") (pin "2") (pinfunction "2_2") (pintype "passive"))
    )
    (net (code "36") (name "Net-(5VLED1-PadA)") (class "Default")
      (node (ref "5VLED1") (pin "A") (pinfunction "A_A") (pintype "passive"))
      (node (ref "5VLEDR1") (pin "2") (pinfunction "2_2") (pintype "passive"))
    )
    (net (code "37") (name "Net-(5VLED2-PadA)") (class "Default")
      (node (ref "5VLED2") (pin "A") (pinfunction "A_A") (pintype "passive"))
      (node (ref "5VLEDR2") (pin "2") (pinfunction "2_2") (pintype "passive"))
    )
    (net (code "38") (name "Net-(5VLED3-PadA)") (class "Default")
      (node (ref "5VLED3") (pin "A") (pinfunction "A_A") (pintype "passive"))
      (node (ref "5VLEDR3") (pin "2") (pinfunction "2_2") (pintype "passive"))
    )
    (net (code "39") (name "Net-(5VLED4-PadA)") (class "Default")
      (node (ref "5VLED4") (pin "A") (pinfunction "A_A") (pintype "passive"))
      (node (ref "5VLEDR4") (pin "2") (pinfunction "2_2") (pintype "passive"))
    )
    (net (code "40") (name "Net-(5VLED5-PadA)") (class "Default")
      (node (ref "5VLED5") (pin "A") (pinfunction "A_A") (pintype "passive"))
      (node (ref "5VLEDR5") (pin "2") (pinfunction "2_2") (pintype "passive"))
    )
    (net (code "41") (name "Net-(5VLED6-PadA)") (class "Default")
      (node (ref "5VLED6") (pin "A") (pinfunction "A_A") (pintype "passive"))
      (node (ref "5VLEDR6") (pin "2") (pinfunction "2_2") (pintype "passive"))
    )
    (net (code "42") (name "Net-(5VLED7-PadA)") (class "Default")
      (node (ref "5VLED7") (pin "A") (pinfunction "A_A") (pintype "passive"))
      (node (ref "5VLEDR7") (pin "2") (pinfunction "2_2") (pintype "passive"))
    )
    (net (code "43") (name "Net-(5VLED8-PadA)") (class "Default")
      (node (ref "5VLED8") (pin "A") (pinfunction "A_A") (pintype "passive"))
      (node (ref "5VLEDR8") (pin "2") (pinfunction "2_2") (pintype "passive"))
    )
    (net (code "44") (name "Net-(5VLED9-PadA)") (class "Default")
      (node (ref "5VLED9") (pin "A") (pinfunction "A_A") (pintype "passive"))
      (node (ref "5VLEDR9") (pin "2") (pinfunction "2_2") (pintype "passive"))
    )
    (net (code "45") (name "Net-(MAINLED-PadA)") (class "Default")
      (node (ref "MAINLED") (pin "A") (pinfunction "A_A") (pintype "passive"))
      (node (ref "MAINLEDR") (pin "2") (pinfunction "2_2") (pintype "passive"))
    )
    (net (code "46") (name "Net-(SC0HVT-D)") (class "Default")
      (node (ref "SC0HVR") (pin "1") (pinfunction "1_1") (pintype "passive"))
      (node (ref "SC0HVT") (pin "3") (pinfunction "D_3") (pintype "bidirectional"))
    )
    (net (code "47") (name "Net-(SC0HVT-G)") (class "Default")
      (node (ref "5VLEDR0") (pin "1") (pinfunction "1_1") (pintype "passive"))
      (node (ref "INOUT0") (pin "4") (pinfunction "4_4") (pintype "bidirectional"))
      (node (ref "SC0HVT") (pin "1") (pinfunction "G_1") (pintype "bidirectional"))
      (node (ref "SC0HVT") (pin "2") (pinfunction "S_2") (pintype "bidirectional"))
      (node (ref "SD0HVT") (pin "1") (pinfunction "G_1") (pintype "bidirectional"))
      (node (ref "SD0HVT") (pin "2") (pinfunction "S_2") (pintype "bidirectional"))
    )
    (net (code "48") (name "Net-(SC0LVT-D)") (class "Default")
      (node (ref "INOUT0") (pin "7") (pinfunction "7_7") (pintype "bidirectional"))
      (node (ref "SC0HVR") (pin "2") (pinfunction "2_2") (pintype "passive"))
      (node (ref "SC0LVT") (pin "3") (pinfunction "D_3") (pintype "bidirectional"))
    )
    (net (code "49") (name "Net-(SC0LVT-G)") (class "Default")
      (node (ref "3.3VREG0") (pin "2") (pinfunction "OUT_2") (pintype "bidirectional"))
      (node (ref "3.3VREG0") (pin "TER") (pinfunction "OUT_TER") (pintype "bidirectional"))
      (node (ref "INOUT0") (pin "6") (pinfunction "6_6") (pintype "bidirectional"))
      (node (ref "SC0LVR") (pin "1") (pinfunction "1_1") (pintype "passive"))
      (node (ref "SC0LVT") (pin "1") (pinfunction "G_1") (pintype "bidirectional"))
      (node (ref "SD0LVR") (pin "1") (pinfunction "1_1") (pintype "passive"))
      (node (ref "SD0LVT") (pin "1") (pinfunction "G_1") (pintype "bidirectional"))
    )
    (net (code "50") (name "Net-(SC1HVT-D)") (class "Default")
      (node (ref "SC1HVR") (pin "1") (pinfunction "1_1") (pintype "passive"))
      (node (ref "SC1HVT") (pin "3") (pinfunction "D_3") (pintype "bidirectional"))
    )
    (net (code "51") (name "Net-(SC1HVT-G)") (class "Default")
      (node (ref "5VLEDR1") (pin "1") (pinfunction "1_1") (pintype "passive"))
      (node (ref "INOUT1") (pin "4") (pinfunction "4_4") (pintype "bidirectional"))
      (node (ref "SC1HVT") (pin "1") (pinfunction "G_1") (pintype "bidirectional"))
      (node (ref "SC1HVT") (pin "2") (pinfunction "S_2") (pintype "bidirectional"))
      (node (ref "SD1HVT") (pin "1") (pinfunction "G_1") (pintype "bidirectional"))
      (node (ref "SD1HVT") (pin "2") (pinfunction "S_2") (pintype "bidirectional"))
    )
    (net (code "52") (name "Net-(SC1LVT-D)") (class "Default")
      (node (ref "INOUT1") (pin "7") (pinfunction "7_7") (pintype "bidirectional"))
      (node (ref "SC1HVR") (pin "2") (pinfunction "2_2") (pintype "passive"))
      (node (ref "SC1LVT") (pin "3") (pinfunction "D_3") (pintype "bidirectional"))
    )
    (net (code "53") (name "Net-(SC1LVT-G)") (class "Default")
      (node (ref "3.3VREG1") (pin "2") (pinfunction "OUT_2") (pintype "bidirectional"))
      (node (ref "3.3VREG1") (pin "TER") (pinfunction "OUT_TER") (pintype "bidirectional"))
      (node (ref "INOUT1") (pin "6") (pinfunction "6_6") (pintype "bidirectional"))
      (node (ref "SC1LVR") (pin "1") (pinfunction "1_1") (pintype "passive"))
      (node (ref "SC1LVT") (pin "1") (pinfunction "G_1") (pintype "bidirectional"))
      (node (ref "SD1LVR") (pin "1") (pinfunction "1_1") (pintype "passive"))
      (node (ref "SD1LVT") (pin "1") (pinfunction "G_1") (pintype "bidirectional"))
    )
    (net (code "54") (name "Net-(SC2HVT-D)") (class "Default")
      (node (ref "SC2HVR") (pin "1") (pinfunction "1_1") (pintype "passive"))
      (node (ref "SC2HVT") (pin "3") (pinfunction "D_3") (pintype "bidirectional"))
    )
    (net (code "55") (name "Net-(SC2HVT-G)") (class "Default")
      (node (ref "5VLEDR2") (pin "1") (pinfunction "1_1") (pintype "passive"))
      (node (ref "INOUT2") (pin "4") (pinfunction "4_4") (pintype "bidirectional"))
      (node (ref "SC2HVT") (pin "1") (pinfunction "G_1") (pintype "bidirectional"))
      (node (ref "SC2HVT") (pin "2") (pinfunction "S_2") (pintype "bidirectional"))
      (node (ref "SD2HVT") (pin "1") (pinfunction "G_1") (pintype "bidirectional"))
      (node (ref "SD2HVT") (pin "2") (pinfunction "S_2") (pintype "bidirectional"))
    )
    (net (code "56") (name "Net-(SC2LVT-D)") (class "Default")
      (node (ref "INOUT2") (pin "7") (pinfunction "7_7") (pintype "bidirectional"))
      (node (ref "SC2HVR") (pin "2") (pinfunction "2_2") (pintype "passive"))
      (node (ref "SC2LVT") (pin "3") (pinfunction "D_3") (pintype "bidirectional"))
    )
    (net (code "57") (name "Net-(SC2LVT-G)") (class "Default")
      (node (ref "3.3VREG2") (pin "2") (pinfunction "OUT_2") (pintype "bidirectional"))
      (node (ref "3.3VREG2") (pin "TER") (pinfunction "OUT_TER") (pintype "bidirectional"))
      (node (ref "INOUT2") (pin "6") (pinfunction "6_6") (pintype "bidirectional"))
      (node (ref "SC2LVR") (pin "1") (pinfunction "1_1") (pintype "passive"))
      (node (ref "SC2LVT") (pin "1") (pinfunction "G_1") (pintype "bidirectional"))
      (node (ref "SD2LVR") (pin "1") (pinfunction "1_1") (pintype "passive"))
      (node (ref "SD2LVT") (pin "1") (pinfunction "G_1") (pintype "bidirectional"))
    )
    (net (code "58") (name "Net-(SC3HVT-D)") (class "Default")
      (node (ref "SC3HVR") (pin "1") (pinfunction "1_1") (pintype "passive"))
      (node (ref "SC3HVT") (pin "3") (pinfunction "D_3") (pintype "bidirectional"))
    )
    (net (code "59") (name "Net-(SC3HVT-G)") (class "Default")
      (node (ref "5VLEDR3") (pin "1") (pinfunction "1_1") (pintype "passive"))
      (node (ref "INOUT3") (pin "4") (pinfunction "4_4") (pintype "bidirectional"))
      (node (ref "SC3HVT") (pin "1") (pinfunction "G_1") (pintype "bidirectional"))
      (node (ref "SC3HVT") (pin "2") (pinfunction "S_2") (pintype "bidirectional"))
      (node (ref "SD3HVT") (pin "1") (pinfunction "G_1") (pintype "bidirectional"))
      (node (ref "SD3HVT") (pin "2") (pinfunction "S_2") (pintype "bidirectional"))
    )
    (net (code "60") (name "Net-(SC3LVT-D)") (class "Default")
      (node (ref "INOUT3") (pin "7") (pinfunction "7_7") (pintype "bidirectional"))
      (node (ref "SC3HVR") (pin "2") (pinfunction "2_2") (pintype "passive"))
      (node (ref "SC3LVT") (pin "3") (pinfunction "D_3") (pintype "bidirectional"))
    )
    (net (code "61") (name "Net-(SC3LVT-G)") (class "Default")
      (node (ref "3.3VREG3") (pin "2") (pinfunction "OUT_2") (pintype "bidirectional"))
      (node (ref "3.3VREG3") (pin "TER") (pinfunction "OUT_TER") (pintype "bidirectional"))
      (node (ref "INOUT3") (pin "6") (pinfunction "6_6") (pintype "bidirectional"))
      (node (ref "SC3LVR") (pin "1") (pinfunction "1_1") (pintype "passive"))
      (node (ref "SC3LVT") (pin "1") (pinfunction "G_1") (pintype "bidirectional"))
      (node (ref "SD3LVR") (pin "1") (pinfunction "1_1") (pintype "passive"))
      (node (ref "SD3LVT") (pin "1") (pinfunction "G_1") (pintype "bidirectional"))
    )
    (net (code "62") (name "Net-(SC4HVT-D)") (class "Default")
      (node (ref "SC4HVR") (pin "1") (pinfunction "1_1") (pintype "passive"))
      (node (ref "SC4HVT") (pin "3") (pinfunction "D_3") (pintype "bidirectional"))
    )
    (net (code "63") (name "Net-(SC4HVT-G)") (class "Default")
      (node (ref "5VLEDR4") (pin "1") (pinfunction "1_1") (pintype "passive"))
      (node (ref "INOUT4") (pin "4") (pinfunction "4_4") (pintype "bidirectional"))
      (node (ref "SC4HVT") (pin "1") (pinfunction "G_1") (pintype "bidirectional"))
      (node (ref "SC4HVT") (pin "2") (pinfunction "S_2") (pintype "bidirectional"))
      (node (ref "SD4HVT") (pin "1") (pinfunction "G_1") (pintype "bidirectional"))
      (node (ref "SD4HVT") (pin "2") (pinfunction "S_2") (pintype "bidirectional"))
    )
    (net (code "64") (name "Net-(SC4LVT-D)") (class "Default")
      (node (ref "INOUT4") (pin "7") (pinfunction "7_7") (pintype "bidirectional"))
      (node (ref "SC4HVR") (pin "2") (pinfunction "2_2") (pintype "passive"))
      (node (ref "SC4LVT") (pin "3") (pinfunction "D_3") (pintype "bidirectional"))
    )
    (net (code "65") (name "Net-(SC4LVT-G)") (class "Default")
      (node (ref "3.3VREG4") (pin "2") (pinfunction "OUT_2") (pintype "bidirectional"))
      (node (ref "3.3VREG4") (pin "TER") (pinfunction "OUT_TER") (pintype "bidirectional"))
      (node (ref "INOUT4") (pin "6") (pinfunction "6_6") (pintype "bidirectional"))
      (node (ref "SC4LVR") (pin "1") (pinfunction "1_1") (pintype "passive"))
      (node (ref "SC4LVT") (pin "1") (pinfunction "G_1") (pintype "bidirectional"))
      (node (ref "SD4LVR") (pin "1") (pinfunction "1_1") (pintype "passive"))
      (node (ref "SD4LVT") (pin "1") (pinfunction "G_1") (pintype "bidirectional"))
    )
    (net (code "66") (name "Net-(SC5HVT-D)") (class "Default")
      (node (ref "SC5HVR") (pin "1") (pinfunction "1_1") (pintype "passive"))
      (node (ref "SC5HVT") (pin "3") (pinfunction "D_3") (pintype "bidirectional"))
    )
    (net (code "67") (name "Net-(SC5HVT-G)") (class "Default")
      (node (ref "5VLEDR5") (pin "1") (pinfunction "1_1") (pintype "passive"))
      (node (ref "INOUT5") (pin "4") (pinfunction "4_4") (pintype "bidirectional"))
      (node (ref "SC5HVT") (pin "1") (pinfunction "G_1") (pintype "bidirectional"))
      (node (ref "SC5HVT") (pin "2") (pinfunction "S_2") (pintype "bidirectional"))
      (node (ref "SD5HVT") (pin "1") (pinfunction "G_1") (pintype "bidirectional"))
      (node (ref "SD5HVT") (pin "2") (pinfunction "S_2") (pintype "bidirectional"))
    )
    (net (code "68") (name "Net-(SC5LVT-D)") (class "Default")
      (node (ref "INOUT5") (pin "7") (pinfunction "7_7") (pintype "bidirectional"))
      (node (ref "SC5HVR") (pin "2") (pinfunction "2_2") (pintype "passive"))
      (node (ref "SC5LVT") (pin "3") (pinfunction "D_3") (pintype "bidirectional"))
    )
    (net (code "69") (name "Net-(SC5LVT-G)") (class "Default")
      (node (ref "3.3VREG5") (pin "2") (pinfunction "OUT_2") (pintype "bidirectional"))
      (node (ref "3.3VREG5") (pin "TER") (pinfunction "OUT_TER") (pintype "bidirectional"))
      (node (ref "INOUT5") (pin "6") (pinfunction "6_6") (pintype "bidirectional"))
      (node (ref "SC5LVR") (pin "1") (pinfunction "1_1") (pintype "passive"))
      (node (ref "SC5LVT") (pin "1") (pinfunction "G_1") (pintype "bidirectional"))
      (node (ref "SD5LVR") (pin "1") (pinfunction "1_1") (pintype "passive"))
      (node (ref "SD5LVT") (pin "1") (pinfunction "G_1") (pintype "bidirectional"))
    )
    (net (code "70") (name "Net-(SC6HVT-D)") (class "Default")
      (node (ref "SC6HVR") (pin "1") (pinfunction "1_1") (pintype "passive"))
      (node (ref "SC6HVT") (pin "3") (pinfunction "D_3") (pintype "bidirectional"))
    )
    (net (code "71") (name "Net-(SC6HVT-G)") (class "Default")
      (node (ref "5VLEDR6") (pin "1") (pinfunction "1_1") (pintype "passive"))
      (node (ref "INOUT6") (pin "4") (pinfunction "4_4") (pintype "bidirectional"))
      (node (ref "SC6HVT") (pin "1") (pinfunction "G_1") (pintype "bidirectional"))
      (node (ref "SC6HVT") (pin "2") (pinfunction "S_2") (pintype "bidirectional"))
      (node (ref "SD6HVT") (pin "1") (pinfunction "G_1") (pintype "bidirectional"))
      (node (ref "SD6HVT") (pin "2") (pinfunction "S_2") (pintype "bidirectional"))
    )
    (net (code "72") (name "Net-(SC6LVT-D)") (class "Default")
      (node (ref "INOUT6") (pin "7") (pinfunction "7_7") (pintype "bidirectional"))
      (node (ref "SC6HVR") (pin "2") (pinfunction "2_2") (pintype "passive"))
      (node (ref "SC6LVT") (pin "3") (pinfunction "D_3") (pintype "bidirectional"))
    )
    (net (code "73") (name "Net-(SC6LVT-G)") (class "Default")
      (node (ref "3.3VREG6") (pin "2") (pinfunction "OUT_2") (pintype "bidirectional"))
      (node (ref "3.3VREG6") (pin "TER") (pinfunction "OUT_TER") (pintype "bidirectional"))
      (node (ref "INOUT6") (pin "6") (pinfunction "6_6") (pintype "bidirectional"))
      (node (ref "SC6LVR") (pin "1") (pinfunction "1_1") (pintype "passive"))
      (node (ref "SC6LVT") (pin "1") (pinfunction "G_1") (pintype "bidirectional"))
      (node (ref "SD6LVR") (pin "1") (pinfunction "1_1") (pintype "passive"))
      (node (ref "SD6LVT") (pin "1") (pinfunction "G_1") (pintype "bidirectional"))
    )
    (net (code "74") (name "Net-(SC7HVT-D)") (class "Default")
      (node (ref "SC7HVR") (pin "1") (pinfunction "1_1") (pintype "passive"))
      (node (ref "SC7HVT") (pin "3") (pinfunction "D_3") (pintype "bidirectional"))
    )
    (net (code "75") (name "Net-(SC7HVT-G)") (class "Default")
      (node (ref "5VLEDR7") (pin "1") (pinfunction "1_1") (pintype "passive"))
      (node (ref "INOUT7") (pin "4") (pinfunction "4_4") (pintype "bidirectional"))
      (node (ref "SC7HVT") (pin "1") (pinfunction "G_1") (pintype "bidirectional"))
      (node (ref "SC7HVT") (pin "2") (pinfunction "S_2") (pintype "bidirectional"))
      (node (ref "SD7HVT") (pin "1") (pinfunction "G_1") (pintype "bidirectional"))
      (node (ref "SD7HVT") (pin "2") (pinfunction "S_2") (pintype "bidirectional"))
    )
    (net (code "76") (name "Net-(SC7LVT-D)") (class "Default")
      (node (ref "INOUT7") (pin "7") (pinfunction "7_7") (pintype "bidirectional"))
      (node (ref "SC7HVR") (pin "2") (pinfunction "2_2") (pintype "passive"))
      (node (ref "SC7LVT") (pin "3") (pinfunction "D_3") (pintype "bidirectional"))
    )
    (net (code "77") (name "Net-(SC7LVT-G)") (class "Default")
      (node (ref "3.3VREG7") (pin "2") (pinfunction "OUT_2") (pintype "bidirectional"))
      (node (ref "3.3VREG7") (pin "TER") (pinfunction "OUT_TER") (pintype "bidirectional"))
      (node (ref "INOUT7") (pin "6") (pinfunction "6_6") (pintype "bidirectional"))
      (node (ref "SC7LVR") (pin "1") (pinfunction "1_1") (pintype "passive"))
      (node (ref "SC7LVT") (pin "1") (pinfunction "G_1") (pintype "bidirectional"))
      (node (ref "SD7LVR") (pin "1") (pinfunction "1_1") (pintype "passive"))
      (node (ref "SD7LVT") (pin "1") (pinfunction "G_1") (pintype "bidirectional"))
    )
    (net (code "78") (name "Net-(SC8HVT-D)") (class "Default")
      (node (ref "SC8HVR") (pin "1") (pinfunction "1_1") (pintype "passive"))
      (node (ref "SC8HVT") (pin "3") (pinfunction "D_3") (pintype "bidirectional"))
    )
    (net (code "79") (name "Net-(SC8HVT-G)") (class "Default")
      (node (ref "5VLEDR8") (pin "1") (pinfunction "1_1") (pintype "passive"))
      (node (ref "INOUT8") (pin "4") (pinfunction "4_4") (pintype "bidirectional"))
      (node (ref "SC8HVT") (pin "1") (pinfunction "G_1") (pintype "bidirectional"))
      (node (ref "SC8HVT") (pin "2") (pinfunction "S_2") (pintype "bidirectional"))
      (node (ref "SD8HVT") (pin "1") (pinfunction "G_1") (pintype "bidirectional"))
      (node (ref "SD8HVT") (pin "2") (pinfunction "S_2") (pintype "bidirectional"))
    )
    (net (code "80") (name "Net-(SC8LVT-D)") (class "Default")
      (node (ref "INOUT8") (pin "7") (pinfunction "7_7") (pintype "bidirectional"))
      (node (ref "SC8HVR") (pin "2") (pinfunction "2_2") (pintype "passive"))
      (node (ref "SC8LVT") (pin "3") (pinfunction "D_3") (pintype "bidirectional"))
    )
    (net (code "81") (name "Net-(SC8LVT-G)") (class "Default")
      (node (ref "3.3VREG8") (pin "2") (pinfunction "OUT_2") (pintype "bidirectional"))
      (node (ref "3.3VREG8") (pin "TER") (pinfunction "OUT_TER") (pintype "bidirectional"))
      (node (ref "INOUT8") (pin "6") (pinfunction "6_6") (pintype "bidirectional"))
      (node (ref "SC8LVR") (pin "1") (pinfunction "1_1") (pintype "passive"))
      (node (ref "SC8LVT") (pin "1") (pinfunction "G_1") (pintype "bidirectional"))
      (node (ref "SD8LVR") (pin "1") (pinfunction "1_1") (pintype "passive"))
      (node (ref "SD8LVT") (pin "1") (pinfunction "G_1") (pintype "bidirectional"))
    )
    (net (code "82") (name "Net-(SC9HVT-D)") (class "Default")
      (node (ref "SC9HVR") (pin "1") (pinfunction "1_1") (pintype "passive"))
      (node (ref "SC9HVT") (pin "3") (pinfunction "D_3") (pintype "bidirectional"))
    )
    (net (code "83") (name "Net-(SC9HVT-G)") (class "Default")
      (node (ref "5VLEDR9") (pin "1") (pinfunction "1_1") (pintype "passive"))
      (node (ref "INOUT9") (pin "4") (pinfunction "4_4") (pintype "bidirectional"))
      (node (ref "SC9HVT") (pin "1") (pinfunction "G_1") (pintype "bidirectional"))
      (node (ref "SC9HVT") (pin "2") (pinfunction "S_2") (pintype "bidirectional"))
      (node (ref "SD9HVT") (pin "1") (pinfunction "G_1") (pintype "bidirectional"))
      (node (ref "SD9HVT") (pin "2") (pinfunction "S_2") (pintype "bidirectional"))
    )
    (net (code "84") (name "Net-(SC9LVT-D)") (class "Default")
      (node (ref "INOUT9") (pin "7") (pinfunction "7_7") (pintype "bidirectional"))
      (node (ref "SC9HVR") (pin "2") (pinfunction "2_2") (pintype "passive"))
      (node (ref "SC9LVT") (pin "3") (pinfunction "D_3") (pintype "bidirectional"))
    )
    (net (code "85") (name "Net-(SC9LVT-G)") (class "Default")
      (node (ref "3.3VREG9") (pin "2") (pinfunction "OUT_2") (pintype "bidirectional"))
      (node (ref "3.3VREG9") (pin "TER") (pinfunction "OUT_TER") (pintype "bidirectional"))
      (node (ref "INOUT9") (pin "6") (pinfunction "6_6") (pintype "bidirectional"))
      (node (ref "SC9LVR") (pin "1") (pinfunction "1_1") (pintype "passive"))
      (node (ref "SC9LVT") (pin "1") (pinfunction "G_1") (pintype "bidirectional"))
      (node (ref "SD9LVR") (pin "1") (pinfunction "1_1") (pintype "passive"))
      (node (ref "SD9LVT") (pin "1") (pinfunction "G_1") (pintype "bidirectional"))
    )
    (net (code "86") (name "Net-(SD0HVT-D)") (class "Default")
      (node (ref "SD0HVR") (pin "1") (pinfunction "1_1") (pintype "passive"))
      (node (ref "SD0HVT") (pin "3") (pinfunction "D_3") (pintype "bidirectional"))
    )
    (net (code "87") (name "Net-(SD0LVT-D)") (class "Default")
      (node (ref "INOUT0") (pin "2") (pinfunction "2_2") (pintype "bidirectional"))
      (node (ref "SD0HVR") (pin "2") (pinfunction "2_2") (pintype "passive"))
      (node (ref "SD0LVT") (pin "3") (pinfunction "D_3") (pintype "bidirectional"))
    )
    (net (code "88") (name "Net-(SD1HVT-D)") (class "Default")
      (node (ref "SD1HVR") (pin "1") (pinfunction "1_1") (pintype "passive"))
      (node (ref "SD1HVT") (pin "3") (pinfunction "D_3") (pintype "bidirectional"))
    )
    (net (code "89") (name "Net-(SD1LVT-D)") (class "Default")
      (node (ref "INOUT1") (pin "2") (pinfunction "2_2") (pintype "bidirectional"))
      (node (ref "SD1HVR") (pin "2") (pinfunction "2_2") (pintype "passive"))
      (node (ref "SD1LVT") (pin "3") (pinfunction "D_3") (pintype "bidirectional"))
    )
    (net (code "90") (name "Net-(SD2HVT-D)") (class "Default")
      (node (ref "SD2HVR") (pin "1") (pinfunction "1_1") (pintype "passive"))
      (node (ref "SD2HVT") (pin "3") (pinfunction "D_3") (pintype "bidirectional"))
    )
    (net (code "91") (name "Net-(SD2LVT-D)") (class "Default")
      (node (ref "INOUT2") (pin "2") (pinfunction "2_2") (pintype "bidirectional"))
      (node (ref "SD2HVR") (pin "2") (pinfunction "2_2") (pintype "passive"))
      (node (ref "SD2LVT") (pin "3") (pinfunction "D_3") (pintype "bidirectional"))
    )
    (net (code "92") (name "Net-(SD3HVT-D)") (class "Default")
      (node (ref "SD3HVR") (pin "1") (pinfunction "1_1") (pintype "passive"))
      (node (ref "SD3HVT") (pin "3") (pinfunction "D_3") (pintype "bidirectional"))
    )
    (net (code "93") (name "Net-(SD3LVT-D)") (class "Default")
      (node (ref "INOUT3") (pin "2") (pinfunction "2_2") (pintype "bidirectional"))
      (node (ref "SD3HVR") (pin "2") (pinfunction "2_2") (pintype "passive"))
      (node (ref "SD3LVT") (pin "3") (pinfunction "D_3") (pintype "bidirectional"))
    )
    (net (code "94") (name "Net-(SD4HVT-D)") (class "Default")
      (node (ref "SD4HVR") (pin "1") (pinfunction "1_1") (pintype "passive"))
      (node (ref "SD4HVT") (pin "3") (pinfunction "D_3") (pintype "bidirectional"))
    )
    (net (code "95") (name "Net-(SD4LVT-D)") (class "Default")
      (node (ref "INOUT4") (pin "2") (pinfunction "2_2") (pintype "bidirectional"))
      (node (ref "SD4HVR") (pin "2") (pinfunction "2_2") (pintype "passive"))
      (node (ref "SD4LVT") (pin "3") (pinfunction "D_3") (pintype "bidirectional"))
    )
    (net (code "96") (name "Net-(SD5HVT-D)") (class "Default")
      (node (ref "SD5HVR") (pin "1") (pinfunction "1_1") (pintype "passive"))
      (node (ref "SD5HVT") (pin "3") (pinfunction "D_3") (pintype "bidirectional"))
    )
    (net (code "97") (name "Net-(SD5LVT-D)") (class "Default")
      (node (ref "INOUT5") (pin "2") (pinfunction "2_2") (pintype "bidirectional"))
      (node (ref "SD5HVR") (pin "2") (pinfunction "2_2") (pintype "passive"))
      (node (ref "SD5LVT") (pin "3") (pinfunction "D_3") (pintype "bidirectional"))
    )
    (net (code "98") (name "Net-(SD6HVT-D)") (class "Default")
      (node (ref "SD6HVR") (pin "1") (pinfunction "1_1") (pintype "passive"))
      (node (ref "SD6HVT") (pin "3") (pinfunction "D_3") (pintype "bidirectional"))
    )
    (net (code "99") (name "Net-(SD6LVT-D)") (class "Default")
      (node (ref "INOUT6") (pin "2") (pinfunction "2_2") (pintype "bidirectional"))
      (node (ref "SD6HVR") (pin "2") (pinfunction "2_2") (pintype "passive"))
      (node (ref "SD6LVT") (pin "3") (pinfunction "D_3") (pintype "bidirectional"))
    )
    (net (code "100") (name "Net-(SD7HVT-D)") (class "Default")
      (node (ref "SD7HVR") (pin "1") (pinfunction "1_1") (pintype "passive"))
      (node (ref "SD7HVT") (pin "3") (pinfunction "D_3") (pintype "bidirectional"))
    )
    (net (code "101") (name "Net-(SD7LVT-D)") (class "Default")
      (node (ref "INOUT7") (pin "2") (pinfunction "2_2") (pintype "bidirectional"))
      (node (ref "SD7HVR") (pin "2") (pinfunction "2_2") (pintype "passive"))
      (node (ref "SD7LVT") (pin "3") (pinfunction "D_3") (pintype "bidirectional"))
    )
    (net (code "102") (name "Net-(SD8HVT-D)") (class "Default")
      (node (ref "SD8HVR") (pin "1") (pinfunction "1_1") (pintype "passive"))
      (node (ref "SD8HVT") (pin "3") (pinfunction "D_3") (pintype "bidirectional"))
    )
    (net (code "103") (name "Net-(SD8LVT-D)") (class "Default")
      (node (ref "INOUT8") (pin "2") (pinfunction "2_2") (pintype "bidirectional"))
      (node (ref "SD8HVR") (pin "2") (pinfunction "2_2") (pintype "passive"))
      (node (ref "SD8LVT") (pin "3") (pinfunction "D_3") (pintype "bidirectional"))
    )
    (net (code "104") (name "Net-(SD9HVT-D)") (class "Default")
      (node (ref "SD9HVR") (pin "1") (pinfunction "1_1") (pintype "passive"))
      (node (ref "SD9HVT") (pin "3") (pinfunction "D_3") (pintype "bidirectional"))
    )
    (net (code "105") (name "Net-(SD9LVT-D)") (class "Default")
      (node (ref "INOUT9") (pin "2") (pinfunction "2_2") (pintype "bidirectional"))
      (node (ref "SD9HVR") (pin "2") (pinfunction "2_2") (pintype "passive"))
      (node (ref "SD9LVT") (pin "3") (pinfunction "D_3") (pintype "bidirectional"))
    )
  )
)
